# Circuito_el_trico.net
KiCad netlist of a schematic drawn in EAGLE
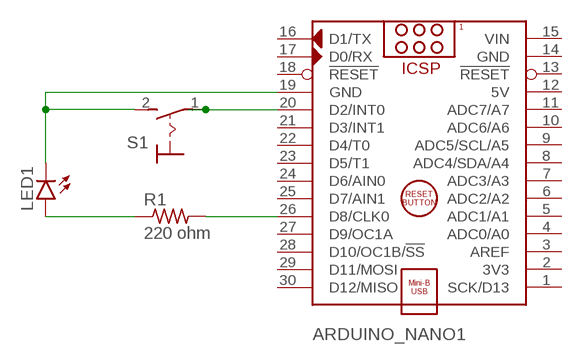
[diagram p0: schematic, sheet 1]

(export (version "E")
  (design (tool "Eeschema 10.0.6"))
  (components
    (comp (ref "ARDUINO_NANO1")
      (value "ARDUINO_NANO")
      (footprint "eagle-import:ARDUINO_NANO")
      (libsource (lib "eagle-import") (part "ARDUINO_NANO"))
    )
    (comp (ref "LED1")
      (value "LED-LUMILED")
      (footprint "eagle-import:LUMILED")
      (libsource (lib "eagle-import") (part "LED-LUMILED"))
    )
    (comp (ref "R1")
      (value "220 ohm")
      (footprint "eagle-import:0204V")
      (libsource (lib "eagle-import") (part "R-US_0204/2V"))
    )
    (comp (ref "S1")
      (value "MS243")
      (footprint "eagle-import:MS243")
      (libsource (lib "eagle-import") (part "MS243"))
    )
  )
  (nets
    (net (code "1") (name "/5V") (class "Default")
      (node (ref "ARDUINO_NANO1") (pin "12") (pinfunction "5V_12") (pintype "power_in"))
    )
    (net (code "2") (name "/GND") (class "Default")
      (node (ref "ARDUINO_NANO1") (pin "14") (pinfunction "GND_14") (pintype "power_in"))
    )
    (net (code "3") (name "/VIN") (class "Default")
      (node (ref "ARDUINO_NANO1") (pin "15") (pinfunction "VIN_15") (pintype "power_in"))
    )
    (net (code "4") (name "Net-(ARDUINO_NANO1-D2{slash}INT0)") (class "Default")
      (node (ref "ARDUINO_NANO1") (pin "20") (pinfunction "D2/INT0_20") (pintype "bidirectional"))
      (node (ref "S1") (pin "1") (pinfunction "P_1") (pintype "passive"))
    )
    (net (code "5") (name "Net-(ARDUINO_NANO1-D8{slash}CLK0)") (class "Default")
      (node (ref "ARDUINO_NANO1") (pin "26") (pinfunction "D8/CLK0_26") (pintype "bidirectional"))
      (node (ref "R1") (pin "2") (pinfunction "2_2") (pintype "passive"))
    )
    (net (code "6") (name "Net-(LED1-A)") (class "Default")
      (node (ref "LED1") (pin "2+") (pinfunction "A_2+") (pintype "passive"))
      (node (ref "R1") (pin "1") (pinfunction "1_1") (pintype "passive"))
    )
    (net (code "7") (name "Net-(LED1-C)") (class "Default")
      (node (ref "ARDUINO_NANO1") (pin "19") (pinfunction "GND_19") (pintype "power_in"))
      (node (ref "LED1") (pin "4-") (pinfunction "C_4-") (pintype "passive"))
      (node (ref "S1") (pin "2") (pinfunction "S_2") (pintype "passive"))
    )
    (net (code "8") (name "unconnected-(ARDUINO_NANO1-3V3-Pad2)") (class "Default")
      (node (ref "ARDUINO_NANO1") (pin "2") (pinfunction "3V3_2") (pintype "output"))
    )
    (net (code "9") (name "unconnected-(ARDUINO_NANO1-ADC0{slash}A0-Pad4)") (class "Default")
      (node (ref "ARDUINO_NANO1") (pin "4") (pinfunction "ADC0/A0_4") (pintype "bidirectional"))
    )
    (net (code "10") (name "unconnected-(ARDUINO_NANO1-ADC1{slash}A1-Pad5)") (class "Default")
      (node (ref "ARDUINO_NANO1") (pin "5") (pinfunction "ADC1/A1_5") (pintype "bidirectional"))
    )
    (net (code "11") (name "unconnected-(ARDUINO_NANO1-ADC2{slash}A2-Pad6)") (class "Default")
      (node (ref "ARDUINO_NANO1") (pin "6") (pinfunction "ADC2/A2_6") (pintype "bidirectional"))
    )
    (net (code "12") (name "unconnected-(ARDUINO_NANO1-ADC3{slash}A3-Pad7)") (class "Default")
      (node (ref "ARDUINO_NANO1") (pin "7") (pinfunction "ADC3/A3_7") (pintype "bidirectional"))
    )
    (net (code "13") (name "unconnected-(ARDUINO_NANO1-ADC4{slash}SDA{slash}A4-Pad8)") (class "Default")
      (node (ref "ARDUINO_NANO1") (pin "8") (pinfunction "ADC4/SDA/A4_8") (pintype "bidirectional"))
    )
    (net (code "14") (name "unconnected-(ARDUINO_NANO1-ADC5{slash}SCL{slash}A5-Pad9)") (class "Default")
      (node (ref "ARDUINO_NANO1") (pin "9") (pinfunction "ADC5/SCL/A5_9") (pintype "bidirectional"))
    )
    (net (code "15") (name "unconnected-(ARDUINO_NANO1-ADC6{slash}A6-Pad10)") (class "Default")
      (node (ref "ARDUINO_NANO1") (pin "10") (pinfunction "ADC6/A6_10") (pintype "bidirectional"))
    )
    (net (code "16") (name "unconnected-(ARDUINO_NANO1-ADC7{slash}A7-Pad11)") (class "Default")
      (node (ref "ARDUINO_NANO1") (pin "11") (pinfunction "ADC7/A7_11") (pintype "bidirectional"))
    )
    (net (code "17") (name "unconnected-(ARDUINO_NANO1-AREF-Pad3)") (class "Default")
      (node (ref "ARDUINO_NANO1") (pin "3") (pinfunction "AREF_3") (pintype "input"))
    )
    (net (code "18") (name "unconnected-(ARDUINO_NANO1-D0{slash}RX-Pad17)") (class "Default")
      (node (ref "ARDUINO_NANO1") (pin "17") (pinfunction "D0/RX_17") (pintype "bidirectional"))
    )
    (net (code "19") (name "unconnected-(ARDUINO_NANO1-D1{slash}TX-Pad16)") (class "Default")
      (node (ref "ARDUINO_NANO1") (pin "16") (pinfunction "D1/TX_16") (pintype "bidirectional"))
    )
    (net (code "20") (name "unconnected-(ARDUINO_NANO1-D3{slash}INT1-Pad21)") (class "Default")
      (node (ref "ARDUINO_NANO1") (pin "21") (pinfunction "D3/INT1_21") (pintype "bidirectional"))
    )
    (net (code "21") (name "unconnected-(ARDUINO_NANO1-D4{slash}T0-Pad22)") (class "Default")
      (node (ref "ARDUINO_NANO1") (pin "22") (pinfunction "D4/T0_22") (pintype "bidirectional"))
    )
    (net (code "22") (name "unconnected-(ARDUINO_NANO1-D5{slash}T1-Pad23)") (class "Default")
      (node (ref "ARDUINO_NANO1") (pin "23") (pinfunction "D5/T1_23") (pintype "bidirectional"))
    )
    (net (code "23") (name "unconnected-(ARDUINO_NANO1-D6{slash}AIN0-Pad24)") (class "Default")
      (node (ref "ARDUINO_NANO1") (pin "24") (pinfunction "D6/AIN0_24") (pintype "bidirectional"))
    )
    (net (code "24") (name "unconnected-(ARDUINO_NANO1-D7{slash}AIN1-Pad25)") (class "Default")
      (node (ref "ARDUINO_NANO1") (pin "25") (pinfunction "D7/AIN1_25") (pintype "bidirectional"))
    )
    (net (code "25") (name "unconnected-(ARDUINO_NANO1-D9{slash}OC1A-Pad27)") (class "Default")
      (node (ref "ARDUINO_NANO1") (pin "27") (pinfunction "D9/OC1A_27") (pintype "bidirectional"))
    )
    (net (code "26") (name "unconnected-(ARDUINO_NANO1-D10{slash}OC1B{slash}~{SS}-Pad28)") (class "Default")
      (node (ref "ARDUINO_NANO1") (pin "28") (pinfunction "D10/OC1B/~{SS}_28") (pintype "bidirectional"))
    )
    (net (code "27") (name "unconnected-(ARDUINO_NANO1-D11{slash}MOSI-Pad29)") (class "Default")
      (node (ref "ARDUINO_NANO1") (pin "29") (pinfunction "D11/MOSI_29") (pintype "bidirectional"))
    )
    (net (code "28") (name "unconnected-(ARDUINO_NANO1-D12{slash}MISO-Pad30)") (class "Default")
      (node (ref "ARDUINO_NANO1") (pin "30") (pinfunction "D12/MISO_30") (pintype "bidirectional"))
    )
    (net (code "29") (name "unconnected-(ARDUINO_NANO1-SCK{slash}D13-Pad1)") (class "Default")
      (node (ref "ARDUINO_NANO1") (pin "1") (pinfunction "SCK/D13_1") (pintype "bidirectional"))
    )
    (net (code "30") (name "unconnected-(ARDUINO_NANO1-~{RESET}-Pad13)") (class "Default")
      (node (ref "ARDUINO_NANO1") (pin "13") (pinfunction "~{RESET}_13") (pintype "input"))
    )
    (net (code "31") (name "unconnected-(ARDUINO_NANO1-~{RESET}-Pad18)") (class "Default")
      (node (ref "ARDUINO_NANO1") (pin "18") (pinfunction "~{RESET}_18") (pintype "input"))
    )
  )
)
